# Training_Board.net
KiCad netlist of a schematic drawn in EAGLE
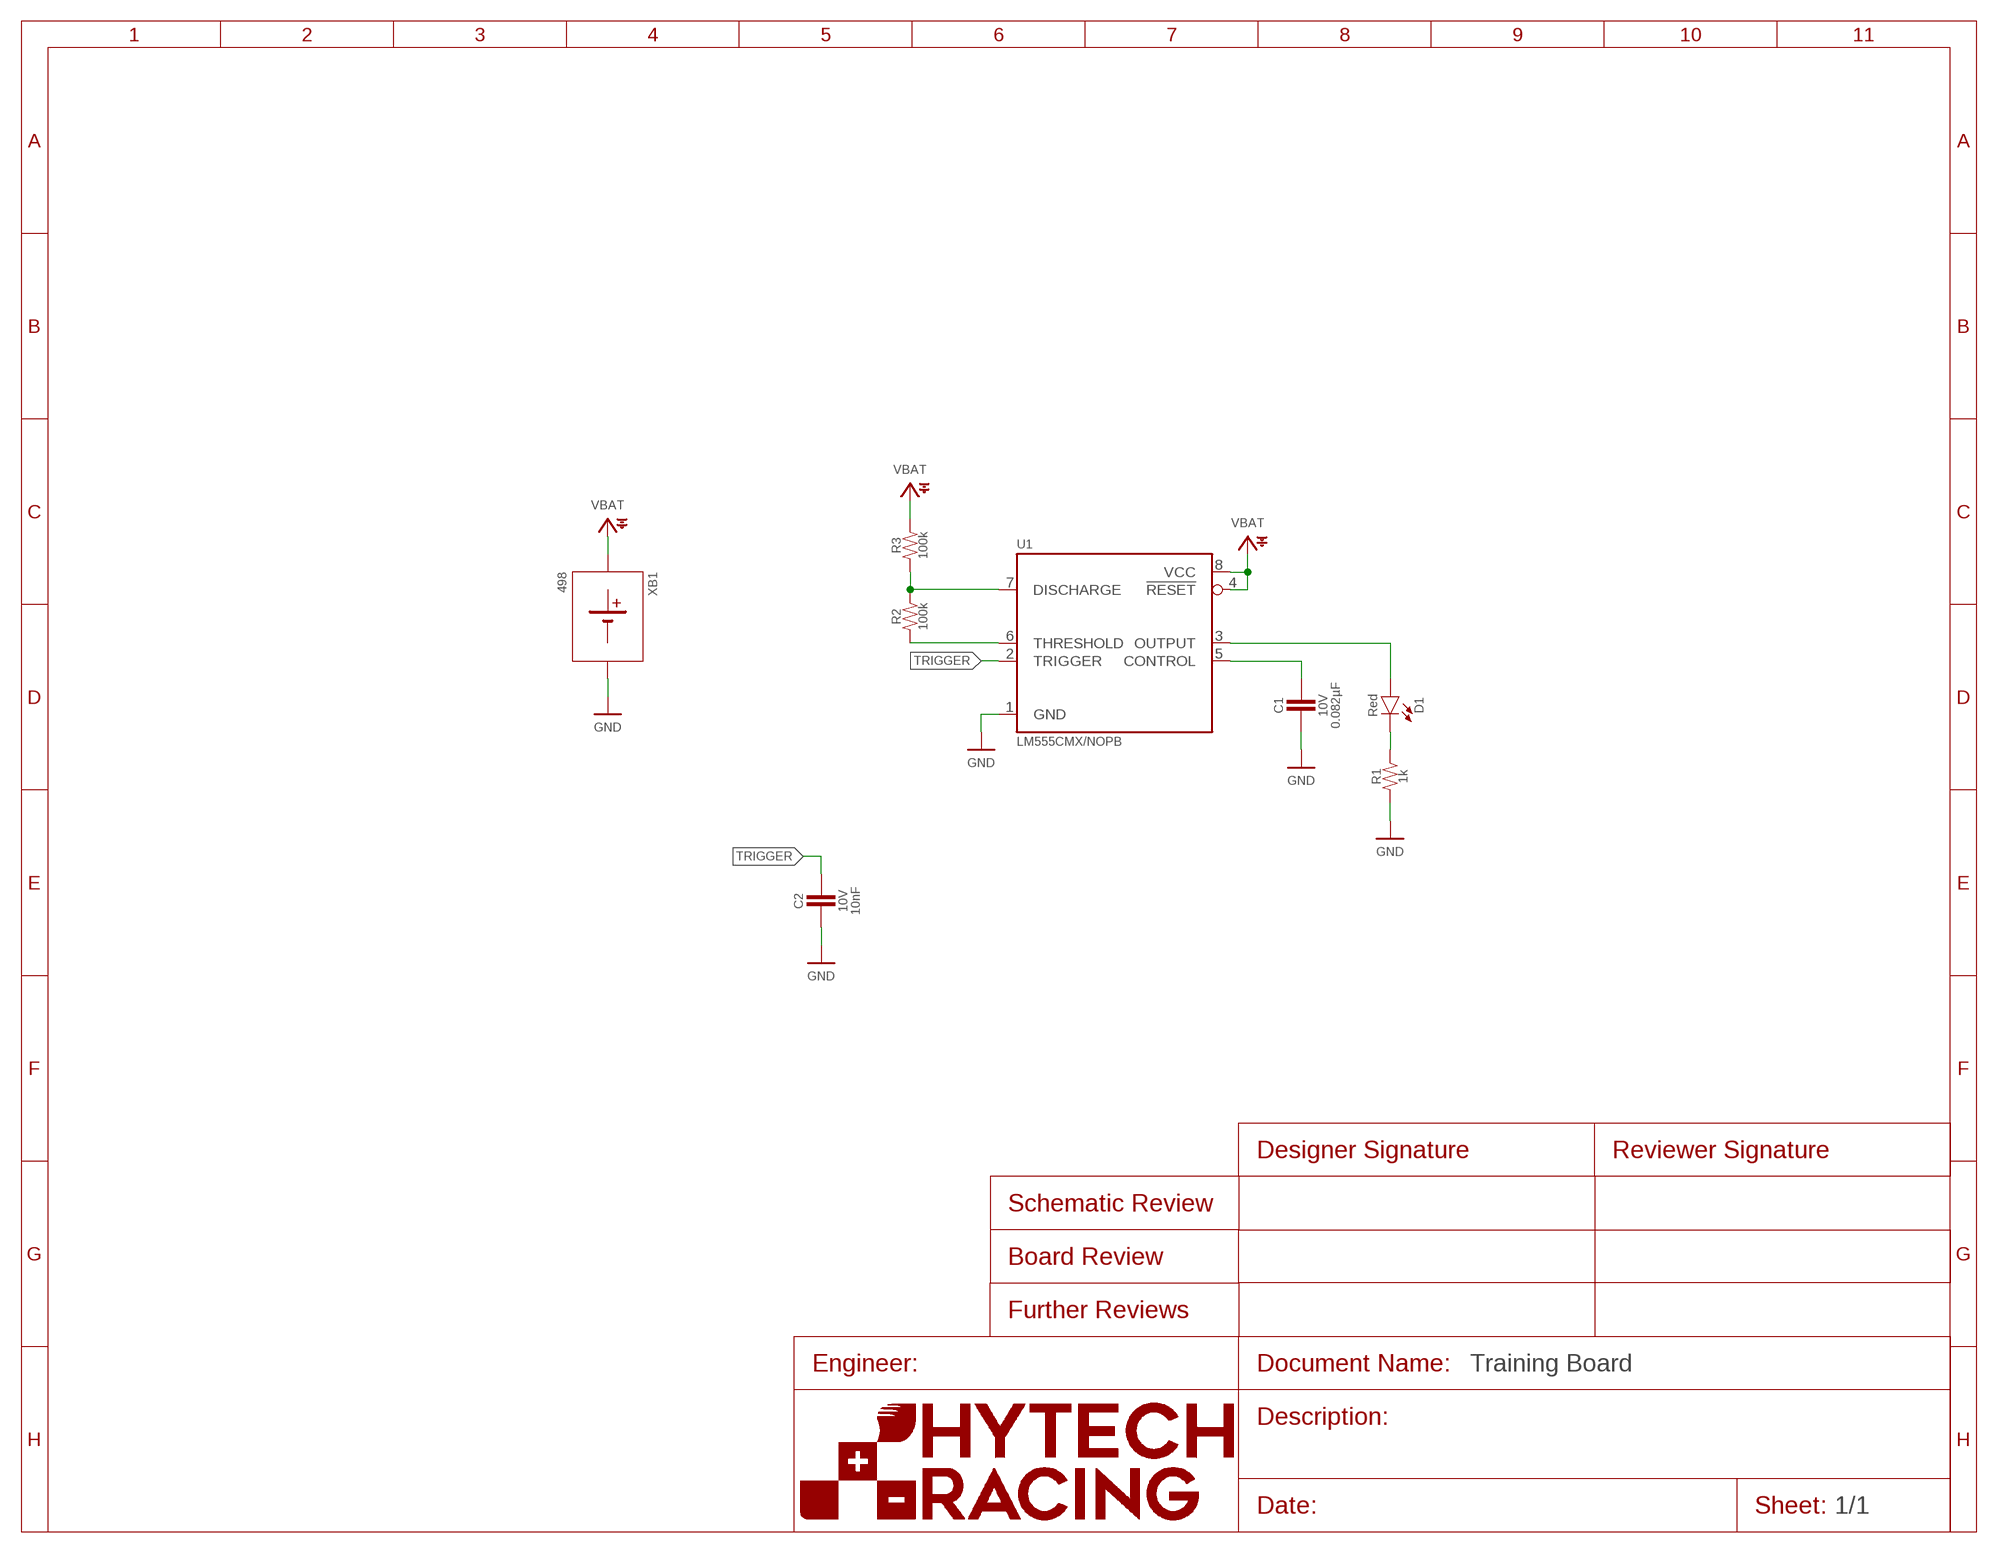
[diagram p0: schematic, sheet 1]

(export (version "E")
  (design (tool "Eeschema 10.0.6"))
  (components
    (comp (ref "C1")
      (value "CAPACITOR_0603_10V_0.082UF")
      (footprint "eagle-import:0603-CAP")
      (fields
        (field (name "CAPACITANCE") "0.082µF")
        (field (name "MANUFACTURER") "KEMET")
        (field (name "MPN") "C0603C823K8RACTU")
        (field (name "TOLERANCE") "10%")
        (field (name "VOLTAGE") "10V")
      )
      (libsource (lib "eagle-import") (part "CAPACITOR_?_060310V_0.082UF"))
    )
    (comp (ref "C2")
      (value "CAPACITOR_0603_10V_10NF")
      (footprint "eagle-import:0603-CAP")
      (fields
        (field (name "CAPACITANCE") "10nF")
        (field (name "MANUFACTURER") "Yageo")
        (field (name "MPN") "CC0603KRX7R6BB103")
        (field (name "TOLERANCE") "10%")
        (field (name "VOLTAGE") "10V")
      )
      (libsource (lib "eagle-import") (part "CAPACITOR_?_060310V_10NF"))
    )
    (comp (ref "D1")
      (value "LED_0603_RED")
      (footprint "eagle-import:0603-LED")
      (fields
        (field (name "COLOR") "Red")
        (field (name "MANUFACTURER") "Kingbright")
        (field (name "MPN") "APT1608SECK/J3-PRV")
      )
      (libsource (lib "eagle-import") (part "LED_?_0603RED"))
    )
    (comp (ref "R1")
      (value "RESISTOR_0603_1K")
      (footprint "eagle-import:0603-RES")
      (fields
        (field (name "MANUFACTURER") "TE Connectivity Passive Product")
        (field (name "MPN") " CPF-A-0603B1K0E")
        (field (name "POWER") "0.0625W")
        (field (name "RESISTANCE") "1k")
      )
      (libsource (lib "eagle-import") (part "RESISTOR_?_06031K"))
    )
    (comp (ref "R2")
      (value "RESISTOR_0603_100K")
      (footprint "eagle-import:0603-RES")
      (fields
        (field (name "MANUFACTURER") "Yageo")
        (field (name "MPN") "RC0603FR-07100KL")
        (field (name "POWER") "0.1W")
        (field (name "RESISTANCE") "100k")
      )
      (libsource (lib "eagle-import") (part "RESISTOR_?_0603100K"))
    )
    (comp (ref "R3")
      (value "RESISTOR_0603_100K")
      (footprint "eagle-import:0603-RES")
      (fields
        (field (name "MANUFACTURER") "Yageo")
        (field (name "MPN") "RC0603FR-07100KL")
        (field (name "POWER") "0.1W")
        (field (name "RESISTANCE") "100k")
      )
      (libsource (lib "eagle-import") (part "RESISTOR_?_0603100K"))
    )
    (comp (ref "U1")
      (value "LM555")
      (footprint "eagle-import:SOIC-08(NARROW,0.15_)")
      (fields (field (name "MANUFACTURER") "Texas Instruments") (field (name "MPN") "LM555CMX/NOPB"))
      (libsource (lib "eagle-import") (part "555LM"))
    )
    (comp (ref "XB1")
      (value "BATTERY_HOLDER_KEYSTONE_498")
      (footprint "eagle-import:498")
      (fields (field (name "MPN") "498") (field (name "MANUFACTURER") "Keystone Electronics"))
      (libsource (lib "eagle-import") (part "BATTERY_HOLDER_KEYSTONE_498"))
    )
  )
  (nets
    (net (code "1") (name "GND") (class "Default")
      (node (ref "C1") (pin "2") (pinfunction "2_2") (pintype "passive"))
      (node (ref "C2") (pin "2") (pinfunction "2_2") (pintype "passive"))
      (node (ref "R1") (pin "1") (pinfunction "1_1") (pintype "passive"))
      (node (ref "U1") (pin "1") (pinfunction "GND_1") (pintype "power_in"))
      (node (ref "XB1") (pin "2") (pinfunction "MINUS_2") (pintype "power_in"))
    )
    (net (code "2") (name "Net-(D1-A)") (class "Default")
      (node (ref "D1") (pin "2") (pinfunction "A_2") (pintype "passive"))
      (node (ref "U1") (pin "3") (pinfunction "OUTPUT_3") (pintype "output"))
    )
    (net (code "3") (name "Net-(D1-C)") (class "Default")
      (node (ref "D1") (pin "1") (pinfunction "C_1") (pintype "passive"))
      (node (ref "R1") (pin "2") (pinfunction "2_2") (pintype "passive"))
    )
    (net (code "4") (name "Net-(U1-CONTROL)") (class "Default")
      (node (ref "C1") (pin "1") (pinfunction "1_1") (pintype "passive"))
      (node (ref "U1") (pin "5") (pinfunction "CONTROL_5") (pintype "input"))
    )
    (net (code "5") (name "Net-(U1-DISCHARGE)") (class "Default")
      (node (ref "R2") (pin "2") (pinfunction "2_2") (pintype "passive"))
      (node (ref "R3") (pin "1") (pinfunction "1_1") (pintype "passive"))
      (node (ref "U1") (pin "7") (pinfunction "DISCHARGE_7") (pintype "input"))
    )
    (net (code "6") (name "Net-(U1-THRESHOLD)") (class "Default")
      (node (ref "R2") (pin "1") (pinfunction "1_1") (pintype "passive"))
      (node (ref "U1") (pin "6") (pinfunction "THRESHOLD_6") (pintype "input"))
    )
    (net (code "7") (name "TRIGGER") (class "Default")
      (node (ref "C2") (pin "1") (pinfunction "1_1") (pintype "passive"))
      (node (ref "U1") (pin "2") (pinfunction "TRIGGER_2") (pintype "input"))
    )
    (net (code "8") (name "VBAT") (class "Default")
      (node (ref "R3") (pin "2") (pinfunction "2_2") (pintype "passive"))
      (node (ref "U1") (pin "4") (pinfunction "~{RESET}_4") (pintype "input"))
      (node (ref "U1") (pin "8") (pinfunction "VCC_8") (pintype "power_in"))
      (node (ref "XB1") (pin "1") (pinfunction "PLUS_1") (pintype "power_in"))
    )
  )
)
